# DCI_TCAN.net
KiCad netlist of a schematic drawn in Altium Designer
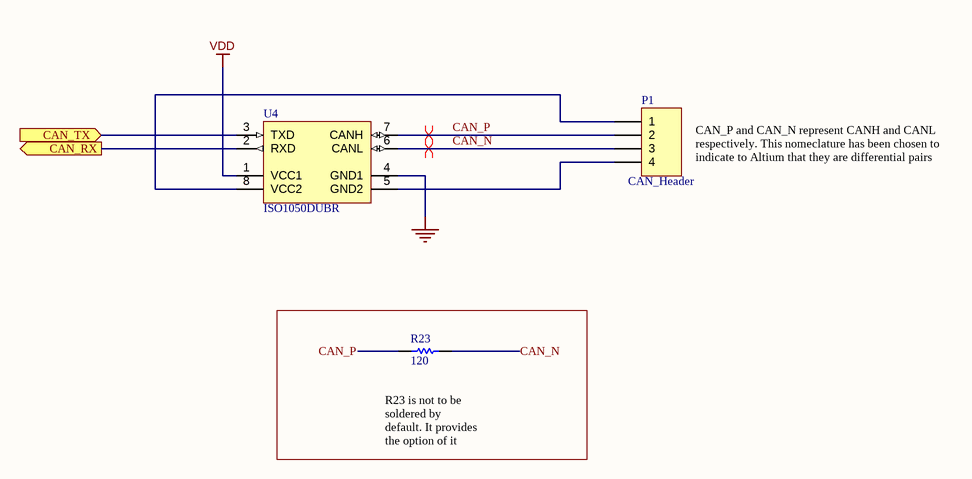
[diagram p0: DCI_TCAN.SchDoc]

(export (version "E")
  (design (tool "Eeschema 10.0.6"))
  (components
    (comp (ref "P1")
      (value "CAN_Header")
      (footprint "HDR1X4")
      (description "Header, 4-Pin")
      (fields (field (name "PUBLISHER") "Altium Limited"))
      (libsource (lib "Miscellaneous Connectors") (part "Header 4"))
    )
    (comp (ref "R23")
      (value "120")
      (footprint "0603R")
      (description "Resistor")
      (fields (field (name "PUBLISHER") "Altium Limited"))
      (libsource (lib "DCI_MB1137") (part "Res1"))
    )
    (comp (ref "U4")
      (value "ISO1050DUBR")
      (footprint "DUB0008A_L")
      (description "Isolated CAN Transceiver, -55 to 105 degC, 8-pin SOP (DUB), Green (RoHS & no Sb/Br)")
      (fields (field (name "MANUFACTURER") "Texas Instruments"))
      (libsource (lib "Altium Content Vault") (part "TI-ISO1050-SOP_DUB-8"))
    )
  )
  (nets
    (net (code "1") (name "/CAN_N") (class "Default")
      (node (ref "P1") (pin "3") (pinfunction "3_3") (pintype "passive"))
      (node (ref "R23") (pin "1") (pinfunction "1_1") (pintype "passive"))
      (node (ref "U4") (pin "6") (pinfunction "CANL_6") (pintype "bidirectional"))
    )
    (net (code "2") (name "/CAN_P") (class "Default")
      (node (ref "P1") (pin "2") (pinfunction "2_2") (pintype "passive"))
      (node (ref "R23") (pin "2") (pinfunction "2_2") (pintype "passive"))
      (node (ref "U4") (pin "7") (pinfunction "CANH_7") (pintype "bidirectional"))
    )
    (net (code "3") (name "/CAN_RX") (class "Default")
      (node (ref "U4") (pin "2") (pinfunction "RXD_2") (pintype "output"))
    )
    (net (code "4") (name "/CAN_TX") (class "Default")
      (node (ref "U4") (pin "3") (pinfunction "TXD_3") (pintype "input"))
    )
    (net (code "5") (name "GND") (class "Default")
      (node (ref "U4") (pin "4") (pinfunction "GND1_4") (pintype "power_in"))
    )
    (net (code "6") (name "Net-(U4-GND2)") (class "Default")
      (node (ref "P1") (pin "4") (pinfunction "4_4") (pintype "passive"))
      (node (ref "U4") (pin "5") (pinfunction "GND2_5") (pintype "power_in"))
    )
    (net (code "7") (name "Net-(U4-VCC2)") (class "Default")
      (node (ref "P1") (pin "1") (pinfunction "1_1") (pintype "passive"))
      (node (ref "U4") (pin "8") (pinfunction "VCC2_8") (pintype "power_in"))
    )
    (net (code "8") (name "VDD") (class "Default")
      (node (ref "U4") (pin "1") (pinfunction "VCC1_1") (pintype "power_in"))
    )
  )
)
